# Striptease-Teensy4_0-v1_2.net
KiCad netlist of a schematic drawn in EAGLE
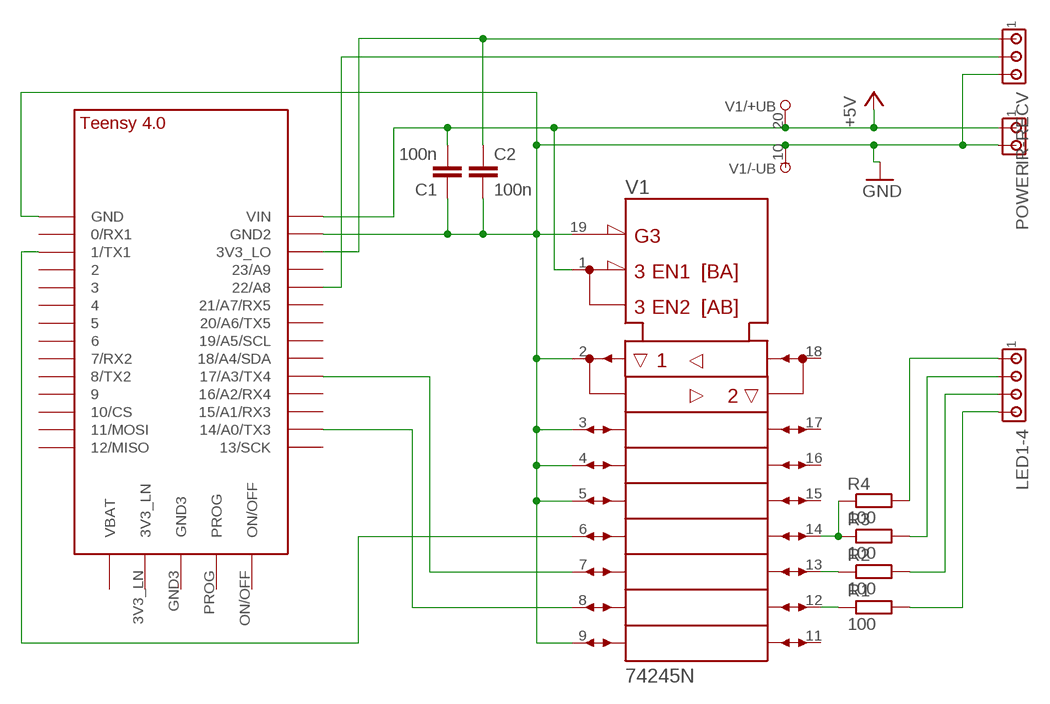
[diagram p0: schematic, sheet 1]

(export (version "E")
  (design (tool "Eeschema 10.0.6"))
  (components
    (comp (ref "C1")
      (value "100n")
      (footprint "eagle-import:C050-025X075")
      (libsource (lib "eagle-import") (part "C-EU050-025X075"))
    )
    (comp (ref "C2")
      (value "100n")
      (footprint "eagle-import:C050-025X075")
      (libsource (lib "eagle-import") (part "C-EU050-025X075"))
    )
    (comp (ref "IR-RECV")
      (value "MTA03-100")
      (footprint "eagle-import:10X03MTA")
      (libsource (lib "eagle-import") (part "MTA03-100"))
    )
    (comp (ref "LED1-4")
      (value "MTA04-100")
      (footprint "eagle-import:10X04MTA")
      (libsource (lib "eagle-import") (part "MTA04-100"))
    )
    (comp (ref "POWER")
      (value "MTA02-100")
      (footprint "eagle-import:10X02MTA")
      (libsource (lib "eagle-import") (part "MTA02-100"))
    )
    (comp (ref "R1")
      (value "100")
      (footprint "eagle-import:0207_10")
      (libsource (lib "eagle-import") (part "R-EU_0207/10"))
    )
    (comp (ref "R2")
      (value "100")
      (footprint "eagle-import:0207_10")
      (libsource (lib "eagle-import") (part "R-EU_0207/10"))
    )
    (comp (ref "R3")
      (value "100")
      (footprint "eagle-import:0207_10")
      (libsource (lib "eagle-import") (part "R-EU_0207/10"))
    )
    (comp (ref "R4")
      (value "100")
      (footprint "eagle-import:0207_10")
      (libsource (lib "eagle-import") (part "R-EU_0207/10"))
    )
    (comp (ref "U$1")
      (value "TEENSY_4.0-BASIC")
      (footprint "eagle-import:TEENSY_4.0-BASIC")
      (libsource (lib "eagle-import") (part "TEENSY_4.0-BASIC"))
    )
    (comp (ref "V1")
      (value "74245N")
      (footprint "eagle-import:DIL20")
      (libsource (lib "eagle-import") (part "74245N"))
    )
  )
  (nets
    (net (code "1") (name "+5V") (class "Default")
      (node (ref "C1") (pin "2") (pinfunction "2_2") (pintype "passive"))
      (node (ref "POWER") (pin "1") (pinfunction "1_1") (pintype "passive"))
      (node (ref "U$1") (pin "VIN") (pinfunction "VIN_VIN") (pintype "bidirectional"))
      (node (ref "V1") (pin "1") (pinfunction "DIR_1") (pintype "input"))
      (node (ref "V1") (pin "20") (pinfunction "+UB_20") (pintype "power_in"))
    )
    (net (code "2") (name "GND") (class "Default")
      (node (ref "C1") (pin "1") (pinfunction "1_1") (pintype "passive"))
      (node (ref "C2") (pin "2") (pinfunction "2_2") (pintype "passive"))
      (node (ref "IR-RECV") (pin "3") (pinfunction "3_3") (pintype "passive"))
      (node (ref "POWER") (pin "2") (pinfunction "2_2") (pintype "passive"))
      (node (ref "U$1") (pin "GND") (pinfunction "GND_GND") (pintype "bidirectional"))
      (node (ref "U$1") (pin "GND2") (pinfunction "GND2_GND2") (pintype "bidirectional"))
      (node (ref "V1") (pin "10") (pinfunction "-UB_10") (pintype "power_in"))
      (node (ref "V1") (pin "19") (pinfunction "~{G}_19") (pintype "input"))
      (node (ref "V1") (pin "2") (pinfunction "A1_2") (pintype "bidirectional"))
      (node (ref "V1") (pin "3") (pinfunction "A2_3") (pintype "bidirectional"))
      (node (ref "V1") (pin "4") (pinfunction "A3_4") (pintype "bidirectional"))
      (node (ref "V1") (pin "5") (pinfunction "A4_5") (pintype "bidirectional"))
      (node (ref "V1") (pin "9") (pinfunction "A8_9") (pintype "bidirectional"))
    )
    (net (code "3") (name "Net-(C2-Pad1)") (class "Default")
      (node (ref "C2") (pin "1") (pinfunction "1_1") (pintype "passive"))
      (node (ref "IR-RECV") (pin "1") (pinfunction "1_1") (pintype "passive"))
      (node (ref "U$1") (pin "3V3_LO") (pinfunction "3V3_LO_3V3_LO") (pintype "bidirectional"))
    )
    (net (code "4") (name "Net-(IR-RECV-Pad2)") (class "Default")
      (node (ref "IR-RECV") (pin "2") (pinfunction "2_2") (pintype "passive"))
      (node (ref "U$1") (pin "22/A8") (pinfunction "22/A8_22/A8") (pintype "bidirectional"))
    )
    (net (code "5") (name "Net-(LED1-4-Pad1)") (class "Default")
      (node (ref "LED1-4") (pin "1") (pinfunction "1_1") (pintype "passive"))
      (node (ref "R4") (pin "2") (pinfunction "2_2") (pintype "passive"))
    )
    (net (code "6") (name "Net-(LED1-4-Pad2)") (class "Default")
      (node (ref "LED1-4") (pin "2") (pinfunction "2_2") (pintype "passive"))
      (node (ref "R3") (pin "2") (pinfunction "2_2") (pintype "passive"))
    )
    (net (code "7") (name "Net-(LED1-4-Pad3)") (class "Default")
      (node (ref "LED1-4") (pin "3") (pinfunction "3_3") (pintype "passive"))
      (node (ref "R2") (pin "2") (pinfunction "2_2") (pintype "passive"))
    )
    (net (code "8") (name "Net-(LED1-4-Pad4)") (class "Default")
      (node (ref "LED1-4") (pin "4") (pinfunction "4_4") (pintype "passive"))
      (node (ref "R1") (pin "2") (pinfunction "2_2") (pintype "passive"))
    )
    (net (code "9") (name "Net-(U$1-1{slash}TX1)") (class "Default")
      (node (ref "U$1") (pin "1/TX") (pinfunction "1/TX1_1/TX") (pintype "bidirectional"))
      (node (ref "V1") (pin "6") (pinfunction "A5_6") (pintype "bidirectional"))
    )
    (net (code "10") (name "Net-(U$1-14{slash}A0{slash}TX3)") (class "Default")
      (node (ref "U$1") (pin "14/A0") (pinfunction "14/A0/TX3_14/A0") (pintype "bidirectional"))
      (node (ref "V1") (pin "8") (pinfunction "A7_8") (pintype "bidirectional"))
    )
    (net (code "11") (name "Net-(U$1-17{slash}A3{slash}TX4)") (class "Default")
      (node (ref "U$1") (pin "17/A3") (pinfunction "17/A3/TX4_17/A3") (pintype "bidirectional"))
      (node (ref "V1") (pin "7") (pinfunction "A6_7") (pintype "bidirectional"))
    )
    (net (code "12") (name "Net-(V1C-B5)") (class "Default")
      (node (ref "R3") (pin "1") (pinfunction "1_1") (pintype "passive"))
      (node (ref "R4") (pin "1") (pinfunction "1_1") (pintype "passive"))
      (node (ref "V1") (pin "14") (pinfunction "B5_14") (pintype "bidirectional"))
    )
    (net (code "13") (name "Net-(V1C-B6)") (class "Default")
      (node (ref "R2") (pin "1") (pinfunction "1_1") (pintype "passive"))
      (node (ref "V1") (pin "13") (pinfunction "B6_13") (pintype "bidirectional"))
    )
    (net (code "14") (name "Net-(V1C-B7)") (class "Default")
      (node (ref "R1") (pin "1") (pinfunction "1_1") (pintype "passive"))
      (node (ref "V1") (pin "12") (pinfunction "B7_12") (pintype "bidirectional"))
    )
    (net (code "15") (name "unconnected-(U$1-0{slash}RX1-Pad0{slash}RX)") (class "Default")
      (node (ref "U$1") (pin "0/RX") (pinfunction "0/RX1_0/RX") (pintype "bidirectional"))
    )
    (net (code "16") (name "unconnected-(U$1-3-Pad3{slash}CANTX)") (class "Default")
      (node (ref "U$1") (pin "3/CANTX") (pinfunction "3_3/CANTX") (pintype "bidirectional"))
    )
    (net (code "17") (name "unconnected-(U$1-4-Pad4{slash}CANRX)") (class "Default")
      (node (ref "U$1") (pin "4/CANRX") (pinfunction "4_4/CANRX") (pintype "bidirectional"))
    )
    (net (code "18") (name "unconnected-(U$1-7{slash}RX2-Pad7)") (class "Default")
      (node (ref "U$1") (pin "7") (pinfunction "7/RX2_7") (pintype "bidirectional"))
    )
    (net (code "19") (name "unconnected-(U$1-8{slash}TX2-Pad8)") (class "Default")
      (node (ref "U$1") (pin "8") (pinfunction "8/TX2_8") (pintype "bidirectional"))
    )
    (net (code "20") (name "unconnected-(U$1-9-Pad9{slash}CS)") (class "Default")
      (node (ref "U$1") (pin "9/CS") (pinfunction "9_9/CS") (pintype "bidirectional"))
    )
    (net (code "21") (name "unconnected-(U$1-15{slash}A1{slash}RX3-Pad15{slash}A1)") (class "Default")
      (node (ref "U$1") (pin "15/A1") (pinfunction "15/A1/RX3_15/A1") (pintype "bidirectional"))
    )
    (net (code "22") (name "unconnected-(U$1-16{slash}A2{slash}RX4-Pad16{slash}A2)") (class "Default")
      (node (ref "U$1") (pin "16/A2") (pinfunction "16/A2/RX4_16/A2") (pintype "bidirectional"))
    )
    (net (code "23") (name "unconnected-(U$1-20{slash}A6{slash}TX5-Pad20{slash}A6)") (class "Default")
      (node (ref "U$1") (pin "20/A6") (pinfunction "20/A6/TX5_20/A6") (pintype "bidirectional"))
    )
    (net (code "24") (name "unconnected-(U$1-21{slash}A7{slash}RX5-Pad21{slash}A7)") (class "Default")
      (node (ref "U$1") (pin "21/A7") (pinfunction "21/A7/RX5_21/A7") (pintype "bidirectional"))
    )
    (net (code "25") (name "unconnected-(U$1-Pad2)") (class "Default")
      (node (ref "U$1") (pin "2") (pinfunction "2_2") (pintype "bidirectional"))
    )
    (net (code "26") (name "unconnected-(U$1-Pad3V3_LN)") (class "Default")
      (node (ref "U$1") (pin "3V3_LN") (pinfunction "3V3_LN_3V3_LN") (pintype "bidirectional"))
    )
    (net (code "27") (name "unconnected-(U$1-Pad5)") (class "Default")
      (node (ref "U$1") (pin "5") (pinfunction "5_5") (pintype "bidirectional"))
    )
    (net (code "28") (name "unconnected-(U$1-Pad6)") (class "Default")
      (node (ref "U$1") (pin "6") (pinfunction "6_6") (pintype "bidirectional"))
    )
    (net (code "29") (name "unconnected-(U$1-Pad10{slash}CS)") (class "Default")
      (node (ref "U$1") (pin "10/CS") (pinfunction "10/CS_10/CS") (pintype "bidirectional"))
    )
    (net (code "30") (name "unconnected-(U$1-Pad11{slash}MOSI)") (class "Default")
      (node (ref "U$1") (pin "11/MOSI") (pinfunction "11/MOSI_11/MOSI") (pintype "bidirectional"))
    )
    (net (code "31") (name "unconnected-(U$1-Pad12{slash}MISO)") (class "Default")
      (node (ref "U$1") (pin "12/MISO") (pinfunction "12/MISO_12/MISO") (pintype "bidirectional"))
    )
    (net (code "32") (name "unconnected-(U$1-Pad13{slash}SCK)") (class "Default")
      (node (ref "U$1") (pin "13/SCK") (pinfunction "13/SCK_13/SCK") (pintype "bidirectional"))
    )
    (net (code "33") (name "unconnected-(U$1-Pad18{slash}A4{slash}SDA)") (class "Default")
      (node (ref "U$1") (pin "18/A4/SDA") (pinfunction "18/A4/SDA_18/A4/SDA") (pintype "bidirectional"))
    )
    (net (code "34") (name "unconnected-(U$1-Pad19{slash}A5{slash}SCL)") (class "Default")
      (node (ref "U$1") (pin "19/A5/SCL") (pinfunction "19/A5/SCL_19/A5/SCL") (pintype "bidirectional"))
    )
    (net (code "35") (name "unconnected-(U$1-Pad23{slash}A9)") (class "Default")
      (node (ref "U$1") (pin "23/A9") (pinfunction "23/A9_23/A9") (pintype "bidirectional"))
    )
    (net (code "36") (name "unconnected-(U$1-PadGND3)") (class "Default")
      (node (ref "U$1") (pin "GND3") (pinfunction "GND3_GND3") (pintype "bidirectional"))
    )
    (net (code "37") (name "unconnected-(U$1-PadON{slash}OFF)") (class "Default")
      (node (ref "U$1") (pin "ON/OFF") (pinfunction "ON/OFF_ON/OFF") (pintype "bidirectional"))
    )
    (net (code "38") (name "unconnected-(U$1-PadPROG)") (class "Default")
      (node (ref "U$1") (pin "PROG") (pinfunction "PROG_PROG") (pintype "bidirectional"))
    )
    (net (code "39") (name "unconnected-(U$1-VBAT-PadVBAT\\)") (class "Default")
      (node (ref "U$1") (pin "VBAT\\") (pinfunction "VBAT_VBAT\\") (pintype "bidirectional"))
    )
    (net (code "40") (name "unconnected-(V1C-B1-Pad18)") (class "Default")
      (node (ref "V1") (pin "18") (pinfunction "B1_18") (pintype "bidirectional"))
    )
    (net (code "41") (name "unconnected-(V1C-B2-Pad17)") (class "Default")
      (node (ref "V1") (pin "17") (pinfunction "B2_17") (pintype "bidirectional"))
    )
    (net (code "42") (name "unconnected-(V1C-B3-Pad16)") (class "Default")
      (node (ref "V1") (pin "16") (pinfunction "B3_16") (pintype "bidirectional"))
    )
    (net (code "43") (name "unconnected-(V1C-B4-Pad15)") (class "Default")
      (node (ref "V1") (pin "15") (pinfunction "B4_15") (pintype "bidirectional"))
    )
    (net (code "44") (name "unconnected-(V1C-B8-Pad11)") (class "Default")
      (node (ref "V1") (pin "11") (pinfunction "B8_11") (pintype "bidirectional"))
    )
  )
)
